# cell_3_2.net
KiCad netlist of a schematic drawn in EAGLE
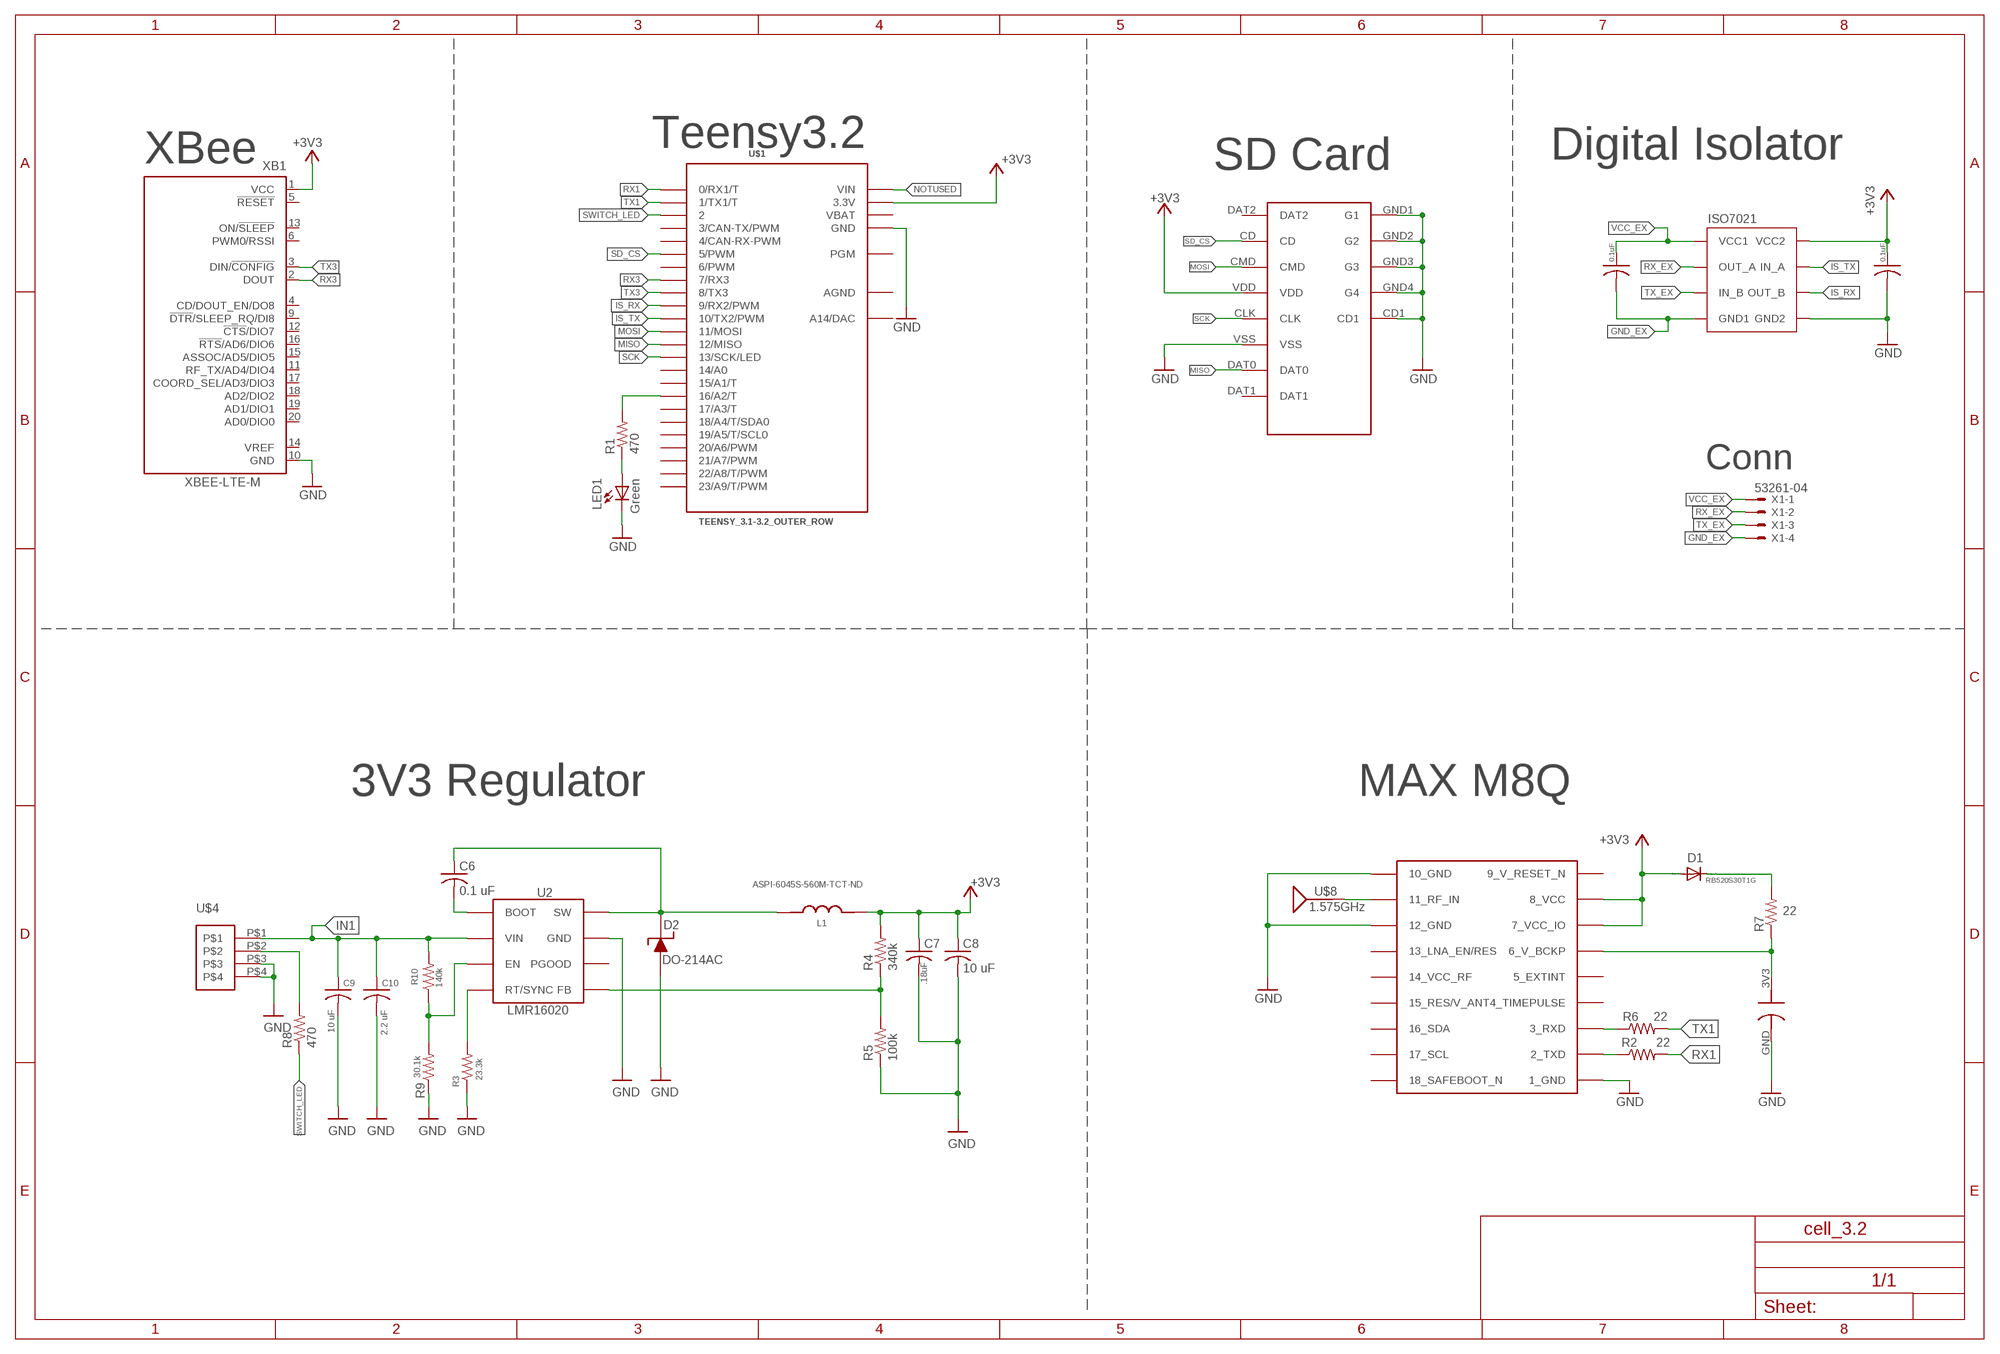
[diagram p0: schematic, sheet 1]

(export (version "E")
  (design (tool "Eeschema 10.0.6"))
  (components
    (comp (ref "C1")
      (value "0.3F")
      (footprint "eagle-import:ELNASUPERCAP")
      (libsource (lib "eagle-import") (part "DCK-3R3E204T614-E"))
    )
    (comp (ref "C2")
      (value "0.1uF")
      (footprint "eagle-import:C0603")
      (libsource (lib "eagle-import") (part "C-USC0603"))
    )
    (comp (ref "C3")
      (value "0.1uF")
      (footprint "eagle-import:C0603")
      (libsource (lib "eagle-import") (part "C-USC0603"))
    )
    (comp (ref "C6")
      (value "0.1 uF")
      (footprint "eagle-import:C0805")
      (libsource (lib "eagle-import") (part "resistor_C-USC0805"))
    )
    (comp (ref "C7")
      (value ".18uF")
      (footprint "eagle-import:C0603")
      (libsource (lib "eagle-import") (part "resistor_C-USC0603"))
    )
    (comp (ref "C8")
      (value "10 uF")
      (footprint "eagle-import:C0603")
      (libsource (lib "eagle-import") (part "resistor_C-USC0603"))
    )
    (comp (ref "C9")
      (value "10 uF")
      (footprint "eagle-import:C1210")
      (libsource (lib "eagle-import") (part "resistor_C-USC1210"))
    )
    (comp (ref "C10")
      (value "2.2 uF")
      (footprint "eagle-import:C1210")
      (libsource (lib "eagle-import") (part "resistor_C-USC1210"))
    )
    (comp (ref "D1")
      (value "RB520S30T1G")
      (footprint "eagle-import:SOD523")
      (libsource (lib "eagle-import") (part "DIODE-SOD523"))
    )
    (comp (ref "D2")
      (value "DO-214AC")
      (footprint "eagle-import:DO-214AC")
      (libsource (lib "eagle-import") (part "DO-214AC"))
    )
    (comp (ref "ISO7021")
      (value "ISO7021")
      (footprint "eagle-import:8-SOIC")
      (libsource (lib "eagle-import") (part "ISO7021"))
    )
    (comp (ref "L1")
      (value "ASPI-6045S-560M-TCT-ND")
      (footprint "eagle-import:ABRACON")
      (libsource (lib "eagle-import") (part "ASPI-6045S-560M-TCT-ND"))
    )
    (comp (ref "LED1")
      (value "Green")
      (footprint "eagle-import:CHIP-LED0603")
      (libsource (lib "eagle-import") (part "LEDCHIP-LED0603"))
    )
    (comp (ref "R1")
      (value "470")
      (footprint "eagle-import:R0603")
      (libsource (lib "eagle-import") (part "resistor_348_R-US_R0603"))
    )
    (comp (ref "R2")
      (value "22")
      (footprint "eagle-import:R0603")
      (libsource (lib "eagle-import") (part "R-US_R0603"))
    )
    (comp (ref "R3")
      (value "23.3k")
      (footprint "eagle-import:R0603")
      (libsource (lib "eagle-import") (part "resistor_R-US_R0603"))
    )
    (comp (ref "R4")
      (value "340k")
      (footprint "eagle-import:R0603")
      (libsource (lib "eagle-import") (part "resistor_R-US_R0603"))
    )
    (comp (ref "R5")
      (value "100k")
      (footprint "eagle-import:R0603")
      (libsource (lib "eagle-import") (part "resistor_R-US_R0603"))
    )
    (comp (ref "R6")
      (value "22")
      (footprint "eagle-import:R0603")
      (libsource (lib "eagle-import") (part "R-US_R0603"))
    )
    (comp (ref "R7")
      (value "22")
      (footprint "eagle-import:R0603")
      (libsource (lib "eagle-import") (part "resistor_348_R-US_R0603"))
    )
    (comp (ref "R8")
      (value "470")
      (footprint "eagle-import:R0603")
      (libsource (lib "eagle-import") (part "resistor_R-US_R0603"))
    )
    (comp (ref "R9")
      (value "30.1k")
      (footprint "eagle-import:R0603")
      (libsource (lib "eagle-import") (part "resistor_R-US_R0603"))
    )
    (comp (ref "R10")
      (value "140k")
      (footprint "eagle-import:R0603")
      (libsource (lib "eagle-import") (part "resistor_R-US_R0603"))
    )
    (comp (ref "U$1")
      (value "TEENSY_3.1-3.2_OUTER_ROW")
      (footprint "eagle-import:TEENSY_3.0-3.2&LC_OUTER_ROW")
      (libsource (lib "eagle-import") (part "TEENSY_3.1-3.2_OUTER_ROW"))
    )
    (comp (ref "U$3")
      (value "MICRO_SD")
      (footprint "eagle-import:MICRO_SD_HINGED")
      (libsource (lib "eagle-import") (part "MICRO_SD"))
    )
    (comp (ref "U$4")
      (value "MICROCLASP_4")
      (footprint "eagle-import:4_PIN_MICROCLASP")
      (libsource (lib "eagle-import") (part "MICROCLASP_4"))
    )
    (comp (ref "U$7")
      (value "MAX-M8")
      (footprint "eagle-import:MAX-M8")
      (libsource (lib "eagle-import") (part "MAX-M8"))
    )
    (comp (ref "U$8")
      (value "1.575GHz")
      (footprint "eagle-import:SPARKFUN-GPS_ANT-GPS-2X7MM")
      (libsource (lib "eagle-import") (part "SPARKFUN-GPS_ANTENNAGPS-2X7MM"))
    )
    (comp (ref "U2")
      (value "LMR16020")
      (footprint "eagle-import:SO8")
      (libsource (lib "eagle-import") (part "LMR16020"))
    )
    (comp (ref "X1")
      (value "53261-04")
      (footprint "eagle-import:53261-04")
      (fields (field (name "MF") "MOLEX"))
      (libsource (lib "eagle-import") (part "53?-04261"))
    )
    (comp (ref "XB1")
      (value "XBEE-LTE-M")
      (footprint "eagle-import:XBEE-PRO")
      (libsource (lib "eagle-import") (part "XBEE-PRO"))
    )
  )
  (nets
    (net (code "1") (name "+3V3") (class "Default")
      (node (ref "C3") (pin "1") (pinfunction "1_1") (pintype "passive"))
      (node (ref "C7") (pin "1") (pinfunction "1_1") (pintype "passive"))
      (node (ref "C8") (pin "1") (pinfunction "1_1") (pintype "passive"))
      (node (ref "D1") (pin "A") (pinfunction "A_A") (pintype "passive"))
      (node (ref "ISO7021") (pin "P$8") (pinfunction "VCC2_P$8") (pintype "bidirectional"))
      (node (ref "L1") (pin "P$2") (pinfunction "P$2_P$2") (pintype "bidirectional"))
      (node (ref "R4") (pin "2") (pinfunction "2_2") (pintype "passive"))
      (node (ref "U$1") (pin "3.3V") (pinfunction "3.3V_3.3V") (pintype "power_in"))
      (node (ref "U$1") (pin "3.3V1") (pinfunction "3.3V_3.3V1") (pintype "power_in"))
      (node (ref "U$3") (pin "VDD") (pinfunction "VDD_VDD") (pintype "bidirectional"))
      (node (ref "U$7") (pin "7_VCC_IO") (pinfunction "7_VCC_IO_7_VCC_IO") (pintype "power_in"))
      (node (ref "U$7") (pin "8_VCC") (pinfunction "8_VCC_8_VCC") (pintype "power_in"))
      (node (ref "XB1") (pin "1") (pinfunction "VCC_1") (pintype "power_in"))
    )
    (net (code "2") (name "/9_V_RESET_N") (class "Default")
      (node (ref "U$7") (pin "9_RESET_N") (pinfunction "9_V_RESET_N_9_RESET_N") (pintype "power_in"))
    )
    (net (code "3") (name "/AGND") (class "Default")
      (node (ref "U$1") (pin "AGND") (pinfunction "AGND_AGND") (pintype "power_in"))
    )
    (net (code "4") (name "/VBAT") (class "Default")
      (node (ref "U$1") (pin "VBAT") (pinfunction "VBAT_VBAT") (pintype "power_in"))
    )
    (net (code "5") (name "GND") (class "Default")
      (node (ref "C1") (pin "GND") (pinfunction "GND_GND") (pintype "bidirectional"))
      (node (ref "C10") (pin "2") (pinfunction "2_2") (pintype "passive"))
      (node (ref "C3") (pin "2") (pinfunction "2_2") (pintype "passive"))
      (node (ref "C7") (pin "2") (pinfunction "2_2") (pintype "passive"))
      (node (ref "C8") (pin "2") (pinfunction "2_2") (pintype "passive"))
      (node (ref "C9") (pin "2") (pinfunction "2_2") (pintype "passive"))
      (node (ref "D2") (pin "P$1") (pinfunction "P$1_P$1") (pintype "bidirectional"))
      (node (ref "ISO7021") (pin "P$5") (pinfunction "GND2_P$5") (pintype "bidirectional"))
      (node (ref "LED1") (pin "C") (pinfunction "C_C") (pintype "passive"))
      (node (ref "R3") (pin "1") (pinfunction "1_1") (pintype "passive"))
      (node (ref "R5") (pin "1") (pinfunction "1_1") (pintype "passive"))
      (node (ref "R9") (pin "1") (pinfunction "1_1") (pintype "passive"))
      (node (ref "U$1") (pin "GND") (pinfunction "GND_GND") (pintype "power_in"))
      (node (ref "U$1") (pin "GND1") (pinfunction "GND_GND1") (pintype "power_in"))
      (node (ref "U$3") (pin "CD1") (pinfunction "CD1_CD1") (pintype "bidirectional"))
      (node (ref "U$3") (pin "GND1") (pinfunction "G1_GND1") (pintype "bidirectional"))
      (node (ref "U$3") (pin "GND2") (pinfunction "G2_GND2") (pintype "bidirectional"))
      (node (ref "U$3") (pin "GND3") (pinfunction "G3_GND3") (pintype "bidirectional"))
      (node (ref "U$3") (pin "GND4") (pinfunction "G4_GND4") (pintype "bidirectional"))
      (node (ref "U$3") (pin "VSS") (pinfunction "VSS_VSS") (pintype "bidirectional"))
      (node (ref "U$4") (pin "P$3") (pinfunction "P$3_P$3") (pintype "bidirectional"))
      (node (ref "U$4") (pin "P$4") (pinfunction "P$4_P$4") (pintype "bidirectional"))
      (node (ref "U$7") (pin "10_GND") (pinfunction "10_GND_10_GND") (pintype "power_in"))
      (node (ref "U$7") (pin "12_GND") (pinfunction "12_GND_12_GND") (pintype "power_in"))
      (node (ref "U$7") (pin "1_GND") (pinfunction "1_GND_1_GND") (pintype "power_in"))
      (node (ref "U2") (pin "P$7") (pinfunction "GND_P$7") (pintype "bidirectional"))
      (node (ref "U2") (pin "PAD") (pinfunction "GND_PAD") (pintype "bidirectional"))
      (node (ref "XB1") (pin "10") (pinfunction "GND_10") (pintype "power_in"))
    )
    (net (code "6") (name "GND_EX") (class "Default")
      (node (ref "C2") (pin "2") (pinfunction "2_2") (pintype "passive"))
      (node (ref "ISO7021") (pin "P$4") (pinfunction "GND1_P$4") (pintype "bidirectional"))
      (node (ref "X1") (pin "4") (pinfunction "S_4") (pintype "passive"))
    )
    (net (code "7") (name "IN1") (class "Default")
      (node (ref "C10") (pin "1") (pinfunction "1_1") (pintype "passive"))
      (node (ref "C9") (pin "1") (pinfunction "1_1") (pintype "passive"))
      (node (ref "R10") (pin "2") (pinfunction "2_2") (pintype "passive"))
      (node (ref "U$4") (pin "P$1") (pinfunction "P$1_P$1") (pintype "bidirectional"))
      (node (ref "U2") (pin "P$2") (pinfunction "VIN_P$2") (pintype "bidirectional"))
    )
    (net (code "8") (name "IS_RX") (class "Default")
      (node (ref "ISO7021") (pin "P$6") (pinfunction "OUT_B_P$6") (pintype "bidirectional"))
      (node (ref "U$1") (pin "9") (pinfunction "9/RX2/PWM_9") (pintype "bidirectional"))
    )
    (net (code "9") (name "IS_TX") (class "Default")
      (node (ref "ISO7021") (pin "P$7") (pinfunction "IN_A_P$7") (pintype "bidirectional"))
      (node (ref "U$1") (pin "10") (pinfunction "10/TX2/PWM_10") (pintype "bidirectional"))
    )
    (net (code "10") (name "MISO") (class "Default")
      (node (ref "U$1") (pin "12") (pinfunction "12/MISO_12") (pintype "bidirectional"))
      (node (ref "U$3") (pin "DAT0") (pinfunction "DAT0_DAT0") (pintype "bidirectional"))
    )
    (net (code "11") (name "MOSI") (class "Default")
      (node (ref "U$1") (pin "11") (pinfunction "11/MOSI_11") (pintype "bidirectional"))
      (node (ref "U$3") (pin "CMD") (pinfunction "CMD_CMD") (pintype "bidirectional"))
    )
    (net (code "12") (name "NOTUSED") (class "Default")
      (node (ref "U$1") (pin "VIN") (pinfunction "VIN_VIN") (pintype "power_in"))
    )
    (net (code "13") (name "Net-(C1-Pad3V3)") (class "Default")
      (node (ref "C1") (pin "3V3") (pinfunction "3V3_3V3") (pintype "bidirectional"))
      (node (ref "R7") (pin "1") (pinfunction "1_1") (pintype "passive"))
      (node (ref "U$7") (pin "6_V_BCKP") (pinfunction "6_V_BCKP_6_V_BCKP") (pintype "bidirectional"))
    )
    (net (code "14") (name "Net-(D1-PadC)") (class "Default")
      (node (ref "D1") (pin "C") (pinfunction "C_C") (pintype "passive"))
      (node (ref "R7") (pin "2") (pinfunction "2_2") (pintype "passive"))
    )
    (net (code "15") (name "Net-(LED1-PadA)") (class "Default")
      (node (ref "LED1") (pin "A") (pinfunction "A_A") (pintype "passive"))
      (node (ref "R1") (pin "1") (pinfunction "1_1") (pintype "passive"))
    )
    (net (code "16") (name "Net-(R2-Pad1)") (class "Default")
      (node (ref "R2") (pin "1") (pinfunction "1_1") (pintype "passive"))
      (node (ref "U$7") (pin "2_TXD") (pinfunction "2_TXD_2_TXD") (pintype "bidirectional"))
    )
    (net (code "17") (name "Net-(R6-Pad1)") (class "Default")
      (node (ref "R6") (pin "1") (pinfunction "1_1") (pintype "passive"))
      (node (ref "U$7") (pin "3_RXD") (pinfunction "3_RXD_3_RXD") (pintype "bidirectional"))
    )
    (net (code "18") (name "Net-(R8-Pad2)") (class "Default")
      (node (ref "R8") (pin "2") (pinfunction "2_2") (pintype "passive"))
      (node (ref "U$4") (pin "P$2") (pinfunction "P$2_P$2") (pintype "bidirectional"))
    )
    (net (code "19") (name "Net-(U$1-16{slash}A2{slash}T)") (class "Default")
      (node (ref "R1") (pin "2") (pinfunction "2_2") (pintype "passive"))
      (node (ref "U$1") (pin "16/A2") (pinfunction "16/A2/T_16/A2") (pintype "bidirectional"))
    )
    (net (code "20") (name "Net-(U$8-SIGNAL)") (class "Default")
      (node (ref "U$7") (pin "11_RF_IN") (pinfunction "11_RF_IN_11_RF_IN") (pintype "bidirectional"))
      (node (ref "U$8") (pin "1") (pinfunction "SIGNAL_1") (pintype "bidirectional"))
    )
    (net (code "21") (name "Net-(U2-BOOT)") (class "Default")
      (node (ref "C6") (pin "2") (pinfunction "2_2") (pintype "passive"))
      (node (ref "U2") (pin "P$1") (pinfunction "BOOT_P$1") (pintype "bidirectional"))
    )
    (net (code "22") (name "Net-(U2-EN)") (class "Default")
      (node (ref "R10") (pin "1") (pinfunction "1_1") (pintype "passive"))
      (node (ref "R9") (pin "2") (pinfunction "2_2") (pintype "passive"))
      (node (ref "U2") (pin "P$3") (pinfunction "EN_P$3") (pintype "bidirectional"))
    )
    (net (code "23") (name "Net-(U2-FB)") (class "Default")
      (node (ref "R4") (pin "1") (pinfunction "1_1") (pintype "passive"))
      (node (ref "R5") (pin "2") (pinfunction "2_2") (pintype "passive"))
      (node (ref "U2") (pin "P$5") (pinfunction "FB_P$5") (pintype "bidirectional"))
    )
    (net (code "24") (name "Net-(U2-RT{slash}SYNC)") (class "Default")
      (node (ref "R3") (pin "2") (pinfunction "2_2") (pintype "passive"))
      (node (ref "U2") (pin "P$4") (pinfunction "RT/SYNC_P$4") (pintype "bidirectional"))
    )
    (net (code "25") (name "Net-(U2-SW)") (class "Default")
      (node (ref "C6") (pin "1") (pinfunction "1_1") (pintype "passive"))
      (node (ref "D2") (pin "P$2") (pinfunction "P$2_P$2") (pintype "bidirectional"))
      (node (ref "L1") (pin "P$1") (pinfunction "P$1_P$1") (pintype "bidirectional"))
      (node (ref "U2") (pin "P$8") (pinfunction "SW_P$8") (pintype "bidirectional"))
    )
    (net (code "26") (name "RX1") (class "Default")
      (node (ref "R2") (pin "2") (pinfunction "2_2") (pintype "passive"))
      (node (ref "U$1") (pin "0") (pinfunction "0/RX1/T_0") (pintype "bidirectional"))
    )
    (net (code "27") (name "RX3") (class "Default")
      (node (ref "U$1") (pin "7") (pinfunction "7/RX3_7") (pintype "bidirectional"))
      (node (ref "XB1") (pin "2") (pinfunction "DOUT_2") (pintype "output"))
    )
    (net (code "28") (name "RX_EX") (class "Default")
      (node (ref "ISO7021") (pin "P$2") (pinfunction "OUT_A_P$2") (pintype "bidirectional"))
      (node (ref "X1") (pin "2") (pinfunction "S_2") (pintype "passive"))
    )
    (net (code "29") (name "SCK") (class "Default")
      (node (ref "U$1") (pin "13") (pinfunction "13/SCK/LED_13") (pintype "bidirectional"))
      (node (ref "U$3") (pin "CLK") (pinfunction "CLK_CLK") (pintype "bidirectional"))
    )
    (net (code "30") (name "SD_CS") (class "Default")
      (node (ref "U$1") (pin "5") (pinfunction "5/PWM_5") (pintype "bidirectional"))
      (node (ref "U$3") (pin "CD") (pinfunction "CD_CD") (pintype "bidirectional"))
    )
    (net (code "31") (name "SWITCH_LED") (class "Default")
      (node (ref "R8") (pin "1") (pinfunction "1_1") (pintype "passive"))
      (node (ref "U$1") (pin "2") (pinfunction "2_2") (pintype "bidirectional"))
    )
    (net (code "32") (name "TX1") (class "Default")
      (node (ref "R6") (pin "2") (pinfunction "2_2") (pintype "passive"))
      (node (ref "U$1") (pin "1") (pinfunction "1/TX1/T_1") (pintype "bidirectional"))
    )
    (net (code "33") (name "TX3") (class "Default")
      (node (ref "U$1") (pin "8") (pinfunction "8/TX3_8") (pintype "bidirectional"))
      (node (ref "XB1") (pin "3") (pinfunction "DIN/~{CONFIG}_3") (pintype "input"))
    )
    (net (code "34") (name "TX_EX") (class "Default")
      (node (ref "ISO7021") (pin "P$3") (pinfunction "IN_B_P$3") (pintype "bidirectional"))
      (node (ref "X1") (pin "3") (pinfunction "S_3") (pintype "passive"))
    )
    (net (code "35") (name "VCC_EX") (class "Default")
      (node (ref "C2") (pin "1") (pinfunction "1_1") (pintype "passive"))
      (node (ref "ISO7021") (pin "P$1") (pinfunction "VCC1_P$1") (pintype "bidirectional"))
      (node (ref "X1") (pin "1") (pinfunction "S_1") (pintype "passive"))
    )
    (net (code "36") (name "unconnected-(U$1-3{slash}CAN-TX{slash}PWM-Pad3)") (class "Default")
      (node (ref "U$1") (pin "3") (pinfunction "3/CAN-TX/PWM_3") (pintype "bidirectional"))
    )
    (net (code "37") (name "unconnected-(U$1-4{slash}CAN-RX-PWM-Pad4)") (class "Default")
      (node (ref "U$1") (pin "4") (pinfunction "4/CAN-RX-PWM_4") (pintype "bidirectional"))
    )
    (net (code "38") (name "unconnected-(U$1-6{slash}PWM-Pad6)") (class "Default")
      (node (ref "U$1") (pin "6") (pinfunction "6/PWM_6") (pintype "bidirectional"))
    )
    (net (code "39") (name "unconnected-(U$1-15{slash}A1{slash}T-Pad15{slash}A1)") (class "Default")
      (node (ref "U$1") (pin "15/A1") (pinfunction "15/A1/T_15/A1") (pintype "bidirectional"))
    )
    (net (code "40") (name "unconnected-(U$1-17{slash}A3{slash}T-Pad17{slash}A3)") (class "Default")
      (node (ref "U$1") (pin "17/A3") (pinfunction "17/A3/T_17/A3") (pintype "bidirectional"))
    )
    (net (code "41") (name "unconnected-(U$1-18{slash}A4{slash}T{slash}SDA0-Pad18{slash}A4)") (class "Default")
      (node (ref "U$1") (pin "18/A4") (pinfunction "18/A4/T/SDA0_18/A4") (pintype "bidirectional"))
    )
    (net (code "42") (name "unconnected-(U$1-19{slash}A5{slash}T{slash}SCL0-Pad19{slash}A5)") (class "Default")
      (node (ref "U$1") (pin "19/A5") (pinfunction "19/A5/T/SCL0_19/A5") (pintype "bidirectional"))
    )
    (net (code "43") (name "unconnected-(U$1-20{slash}A6{slash}PWM-Pad20{slash}A6)") (class "Default")
      (node (ref "U$1") (pin "20/A6") (pinfunction "20/A6/PWM_20/A6") (pintype "bidirectional"))
    )
    (net (code "44") (name "unconnected-(U$1-21{slash}A7{slash}PWM-Pad21{slash}A7)") (class "Default")
      (node (ref "U$1") (pin "21/A7") (pinfunction "21/A7/PWM_21/A7") (pintype "bidirectional"))
    )
    (net (code "45") (name "unconnected-(U$1-22{slash}A8{slash}T{slash}PWM-Pad22{slash}A8)") (class "Default")
      (node (ref "U$1") (pin "22/A8") (pinfunction "22/A8/T/PWM_22/A8") (pintype "bidirectional"))
    )
    (net (code "46") (name "unconnected-(U$1-23{slash}A9{slash}T{slash}PWM-Pad23{slash}A9)") (class "Default")
      (node (ref "U$1") (pin "23/A9") (pinfunction "23/A9/T/PWM_23/A9") (pintype "bidirectional"))
    )
    (net (code "47") (name "unconnected-(U$1-A14{slash}DAC-PadRESET{slash}DAC)") (class "Default")
      (node (ref "U$1") (pin "RESET/DAC") (pinfunction "A14/DAC_RESET/DAC") (pintype "bidirectional"))
    )
    (net (code "48") (name "unconnected-(U$1-Pad14{slash}A0)") (class "Default")
      (node (ref "U$1") (pin "14/A0") (pinfunction "14/A0_14/A0") (pintype "bidirectional"))
    )
    (net (code "49") (name "unconnected-(U$1-PadPGM)") (class "Default")
      (node (ref "U$1") (pin "PGM") (pinfunction "PGM_PGM") (pintype "bidirectional"))
    )
    (net (code "50") (name "unconnected-(U$3-PadDAT1)") (class "Default")
      (node (ref "U$3") (pin "DAT1") (pinfunction "DAT1_DAT1") (pintype "bidirectional"))
    )
    (net (code "51") (name "unconnected-(U$3-PadDAT2)") (class "Default")
      (node (ref "U$3") (pin "DAT2") (pinfunction "DAT2_DAT2") (pintype "bidirectional"))
    )
    (net (code "52") (name "unconnected-(U$7-13_LNA_EN{slash}RES-Pad13_LNA_EN)") (class "Default")
      (node (ref "U$7") (pin "13_LNA_EN") (pinfunction "13_LNA_EN/RES_13_LNA_EN") (pintype "bidirectional"))
    )
    (net (code "53") (name "unconnected-(U$7-15_RES{slash}V_ANT-Pad15_V_ANT{slash}RESERVED)") (class "Default")
      (node (ref "U$7") (pin "15_V_ANT/RESERVED") (pinfunction "15_RES/V_ANT_15_V_ANT/RESERVED") (pintype "bidirectional"))
    )
    (net (code "54") (name "unconnected-(U$7-Pad4_TIMEPULSE)") (class "Default")
      (node (ref "U$7") (pin "4_TIMEPULSE") (pinfunction "4_TIMEPULSE_4_TIMEPULSE") (pintype "bidirectional"))
    )
    (net (code "55") (name "unconnected-(U$7-Pad5_EXTINT)") (class "Default")
      (node (ref "U$7") (pin "5_EXTINT") (pinfunction "5_EXTINT_5_EXTINT") (pintype "bidirectional"))
    )
    (net (code "56") (name "unconnected-(U$7-Pad14_VCC_RF)") (class "Default")
      (node (ref "U$7") (pin "14_VCC_RF") (pinfunction "14_VCC_RF_14_VCC_RF") (pintype "bidirectional"))
    )
    (net (code "57") (name "unconnected-(U$7-Pad16_SDA)") (class "Default")
      (node (ref "U$7") (pin "16_SDA") (pinfunction "16_SDA_16_SDA") (pintype "bidirectional"))
    )
    (net (code "58") (name "unconnected-(U$7-Pad17_SCL)") (class "Default")
      (node (ref "U$7") (pin "17_SCL") (pinfunction "17_SCL_17_SCL") (pintype "bidirectional"))
    )
    (net (code "59") (name "unconnected-(U$7-Pad18_SAFEBOOT_N)") (class "Default")
      (node (ref "U$7") (pin "18_SAFEBOOT_N") (pinfunction "18_SAFEBOOT_N_18_SAFEBOOT_N") (pintype "bidirectional"))
    )
    (net (code "60") (name "unconnected-(U2-PGOOD-PadP$6)") (class "Default")
      (node (ref "U2") (pin "P$6") (pinfunction "PGOOD_P$6") (pintype "bidirectional"))
    )
    (net (code "61") (name "unconnected-(XB1-AD0{slash}DIO0-Pad20)") (class "Default")
      (node (ref "XB1") (pin "20") (pinfunction "AD0/DIO0_20") (pintype "bidirectional"))
    )
    (net (code "62") (name "unconnected-(XB1-AD1{slash}DIO1-Pad19)") (class "Default")
      (node (ref "XB1") (pin "19") (pinfunction "AD1/DIO1_19") (pintype "bidirectional"))
    )
    (net (code "63") (name "unconnected-(XB1-AD2{slash}DIO2-Pad18)") (class "Default")
      (node (ref "XB1") (pin "18") (pinfunction "AD2/DIO2_18") (pintype "bidirectional"))
    )
    (net (code "64") (name "unconnected-(XB1-ASSOC{slash}AD5{slash}DIO5-Pad15)") (class "Default")
      (node (ref "XB1") (pin "15") (pinfunction "ASSOC/AD5/DIO5_15") (pintype "bidirectional"))
    )
    (net (code "65") (name "unconnected-(XB1-CD{slash}DOUT_EN{slash}DO8-Pad4)") (class "Default")
      (node (ref "XB1") (pin "4") (pinfunction "CD/DOUT_EN/DO8_4") (pintype "output"))
    )
    (net (code "66") (name "unconnected-(XB1-COORD_SEL{slash}AD3{slash}DIO3-Pad17)") (class "Default")
      (node (ref "XB1") (pin "17") (pinfunction "COORD_SEL/AD3/DIO3_17") (pintype "bidirectional"))
    )
    (net (code "67") (name "unconnected-(XB1-ON{slash}~{SLEEP}-Pad13)") (class "Default")
      (node (ref "XB1") (pin "13") (pinfunction "ON/~{SLEEP}_13") (pintype "output"))
    )
    (net (code "68") (name "unconnected-(XB1-PWM0{slash}RSSI-Pad6)") (class "Default")
      (node (ref "XB1") (pin "6") (pinfunction "PWM0/RSSI_6") (pintype "output"))
    )
    (net (code "69") (name "unconnected-(XB1-RF_TX{slash}AD4{slash}DIO4-Pad11)") (class "Default")
      (node (ref "XB1") (pin "11") (pinfunction "RF_TX/AD4/DIO4_11") (pintype "bidirectional"))
    )
    (net (code "70") (name "unconnected-(XB1-VREF-Pad14)") (class "Default")
      (node (ref "XB1") (pin "14") (pinfunction "VREF_14") (pintype "input"))
    )
    (net (code "71") (name "unconnected-(XB1-~{CTS}{slash}DIO7-Pad12)") (class "Default")
      (node (ref "XB1") (pin "12") (pinfunction "~{CTS}/DIO7_12") (pintype "bidirectional"))
    )
    (net (code "72") (name "unconnected-(XB1-~{DTR}{slash}SLEEP_RQ{slash}DI8-Pad9)") (class "Default")
      (node (ref "XB1") (pin "9") (pinfunction "~{DTR}/SLEEP_RQ/DI8_9") (pintype "bidirectional"))
    )
    (net (code "73") (name "unconnected-(XB1-~{RESET}-Pad5)") (class "Default")
      (node (ref "XB1") (pin "5") (pinfunction "~{RESET}_5") (pintype "input"))
    )
    (net (code "74") (name "unconnected-(XB1-~{RTS}{slash}AD6{slash}DIO6-Pad16)") (class "Default")
      (node (ref "XB1") (pin "16") (pinfunction "~{RTS}/AD6/DIO6_16") (pintype "bidirectional"))
    )
  )
)
